# 3_CAN.net
KiCad netlist of a schematic drawn in Altium Designer
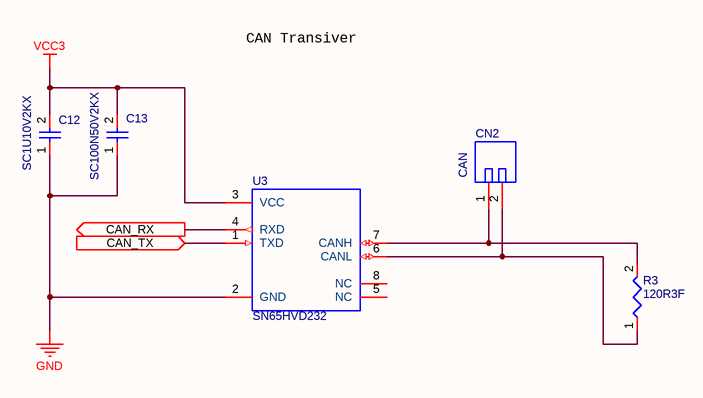
[diagram p0: 3_CAN.SchDoc]

(export (version "E")
  (design (tool "Eeschema 10.0.6"))
  (components
    (comp (ref "C12")
      (value "SC1U10V2KX")
      (footprint "CAPC0402(1005)60_L")
      (description "CAP 1uF 10V ±10% 0402 (1005 Metric) Thickness 0.6mm SMD")
      (libsource (lib "PUMAlib") (part "CAP(0402)1UF10V"))
    )
    (comp (ref "C13")
      (value "SC100N50V2KX")
      (footprint "CAPC0402(1005)60_L")
      (description "CAP 100nF 50V ±10% 0402 (1005 Metric) Thickness 0.6mm SMD")
      (libsource (lib "PUMAlib") (part "CAP(0402)100nF50V"))
    )
    (comp (ref "CN2")
      (value "CAN")
      (footprint "2PHEADERS-2D54")
      (description "2 holes for 18awg wire")
      (fields (field (name "MANUFACTURER") "JST"))
      (libsource (lib "PUMAlib") (part "2PIN-CN"))
    )
    (comp (ref "R3")
      (value "120R3F")
      (footprint "RESC0603(1608)_L")
      (description "120R 0.1W 1% 0603 (1608 Metric)  SMD")
      (libsource (lib "PUMAlib") (part "RES0(0603)_120R"))
    )
    (comp (ref "U3")
      (value "SN65HVD232")
      (footprint "SOIC127P600X175-8L")
      (description "IC CAN TRANSCEIVER 8-SOIC")
      (libsource (lib "PUMAlib") (part "CAN_SN65HVD232D"))
    )
  )
  (nets
    (net (code "1") (name "/CAN_RX") (class "Default")
      (node (ref "U3") (pin "4") (pinfunction "RXD_4") (pintype "output"))
    )
    (net (code "2") (name "/CAN_TX") (class "Default")
      (node (ref "U3") (pin "1") (pinfunction "TXD_1") (pintype "input"))
    )
    (net (code "3") (name "GND") (class "Default")
      (node (ref "C12") (pin "1") (pinfunction "1_1") (pintype "passive"))
      (node (ref "C13") (pin "1") (pinfunction "1_1") (pintype "passive"))
      (node (ref "U3") (pin "2") (pinfunction "GND_2") (pintype "power_in"))
    )
    (net (code "4") (name "Net-(U3-CANH)") (class "Default")
      (node (ref "CN2") (pin "1") (pinfunction "1_1") (pintype "passive"))
      (node (ref "R3") (pin "2") (pinfunction "2_2") (pintype "passive"))
      (node (ref "U3") (pin "7") (pinfunction "CANH_7") (pintype "bidirectional"))
    )
    (net (code "5") (name "Net-(U3-CANL)") (class "Default")
      (node (ref "CN2") (pin "2") (pinfunction "2_2") (pintype "passive"))
      (node (ref "R3") (pin "1") (pinfunction "1_1") (pintype "passive"))
      (node (ref "U3") (pin "6") (pinfunction "CANL_6") (pintype "bidirectional"))
    )
    (net (code "6") (name "VCC3") (class "Default")
      (node (ref "C12") (pin "2") (pinfunction "2_2") (pintype "passive"))
      (node (ref "C13") (pin "2") (pinfunction "2_2") (pintype "passive"))
      (node (ref "U3") (pin "3") (pinfunction "VCC_3") (pintype "power_in"))
    )
    (net (code "7") (name "unconnected-(U3-NC-Pad5)") (class "Default")
      (node (ref "U3") (pin "5") (pinfunction "NC_5") (pintype "passive"))
    )
    (net (code "8") (name "unconnected-(U3-NC-Pad8)") (class "Default")
      (node (ref "U3") (pin "8") (pinfunction "NC_8") (pintype "passive"))
    )
  )
)
